# team_throttle_control_draft_2.net
KiCad netlist of a schematic drawn in Altium Designer
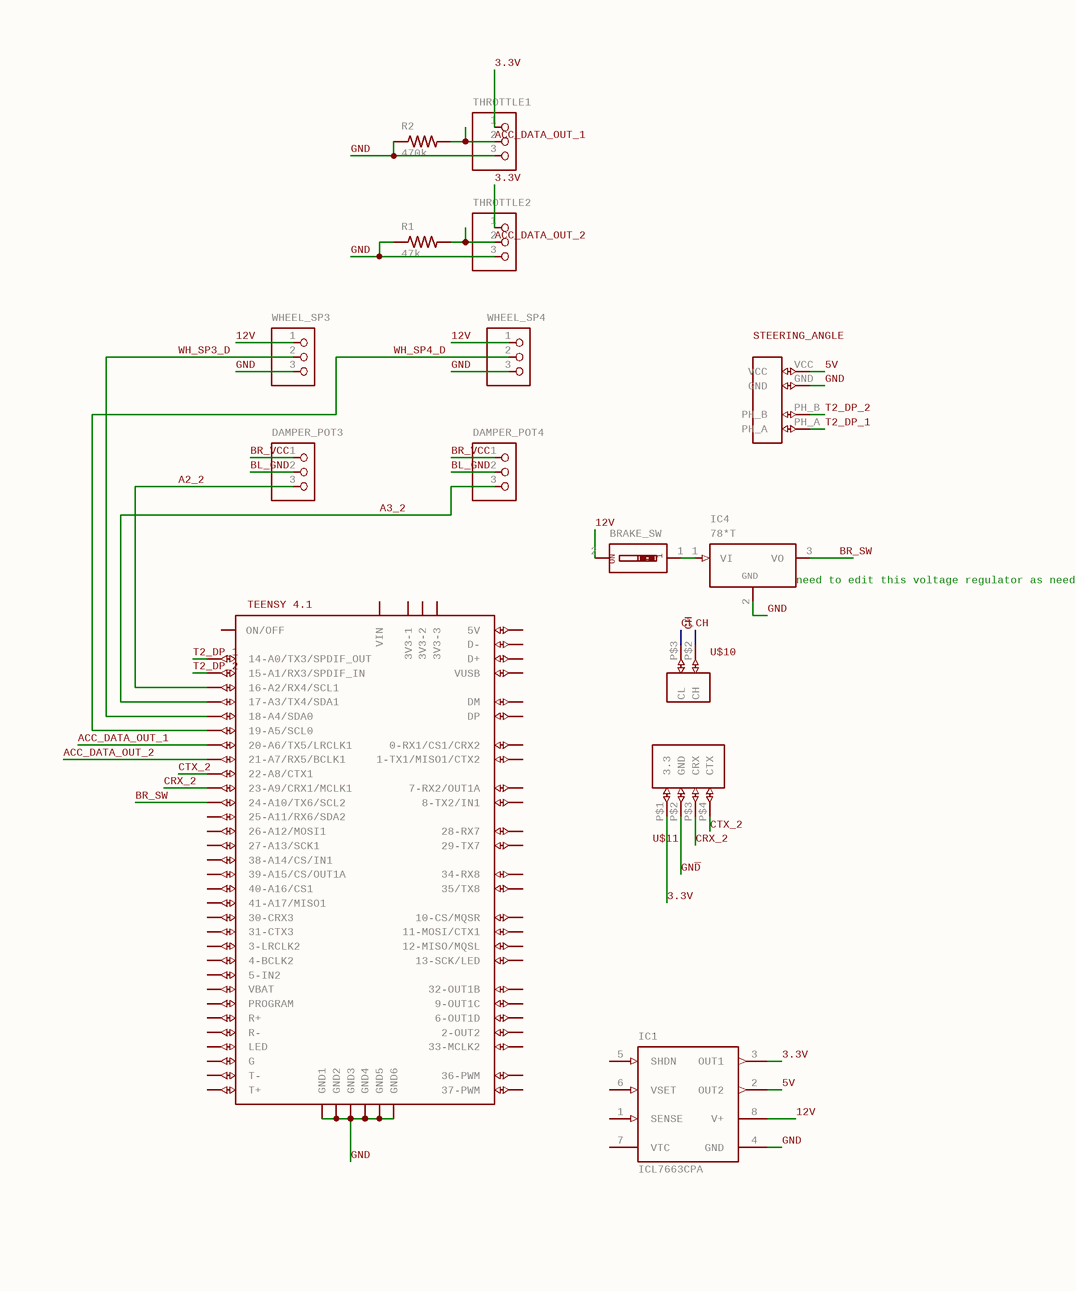
[diagram p0: team throttle control draft 2.SchDoc]

(export (version "E")
  (design (tool "Eeschema 10.0.6"))
  (components
    (comp (ref "BRAKE_SW")
      (value "SW_DIP-1")
      (footprint "EDG-01")
      (description "DIP SWITCH")
      (fields (field (name "1") "1") (field (name "ON") "ON"))
      (libsource (lib "special") (part "SW_DIP-1"))
    )
    (comp (ref "DAMPER_POT3")
      (value "PINHD-1X3CB")
      (footprint "1X03-CLEANBIG")
      (description "PIN HEADER")
      (libsource (lib "adafruit") (part "PINHD-1X3CB"))
    )
    (comp (ref "DAMPER_POT4")
      (value "PINHD-1X3CB")
      (footprint "1X03-CLEANBIG")
      (description "PIN HEADER")
      (libsource (lib "adafruit") (part "PINHD-1X3CB"))
    )
    (comp (ref "IC1")
      (value "ICL7663CPA")
      (footprint "DIL08")
      (description "Positive VOLTAGE REGULATOR")
      (fields (field (name "MF") "MF") (field (name "MPN") "MPN"))
      (libsource (lib "maxim") (part "ICL7663CPA"))
    )
    (comp (ref "IC4")
      (value "78*T")
      (footprint "TO220H")
      (description "Positive VOLTAGE REGULATOR   Added bigger pads to the TO-92 package")
      (fields (field (name "GND") "GND"))
      (libsource (lib "adafruit") (part "78*T"))
    )
    (comp (ref "R1")
      (value "47k")
      (footprint "0204/7")
      (description "RESISTOR, American symbol")
      (libsource (lib "rcl") (part "R-US_0204/7"))
    )
    (comp (ref "R2")
      (value "470k")
      (footprint "0204/7")
      (description "RESISTOR, American symbol")
      (libsource (lib "rcl") (part "R-US_0204/7"))
    )
    (comp (ref "STEERING_ANGLE")
      (value "ROTARY_ENCODER")
      (footprint "ROTARY_ENCODER")
      (libsource (lib "F-E library custom components") (part "ROTARY_ENCODER"))
    )
    (comp (ref "THROTTLE1")
      (value "PINHD-1X3")
      (footprint "1X03")
      (description "PIN HEADER")
      (libsource (lib "adafruit") (part "PINHD-1X3"))
    )
    (comp (ref "THROTTLE2")
      (value "PINHD-1X3")
      (footprint "1X03")
      (description "PIN HEADER")
      (libsource (lib "adafruit") (part "PINHD-1X3"))
    )
    (comp (ref "U$3")
      (value "TEENSY41")
      (footprint "TEENSY41")
      (fields (field (name "TEENSY4.1") "TEENSY 4.1"))
      (libsource (lib "teensy") (part "TEENSY41"))
    )
    (comp (ref "U$10")
      (value "CAN_BUS")
      (footprint "CAN_BUS")
      (libsource (lib "F-E library custom components") (part "CAN_BUS"))
    )
    (comp (ref "U$11")
      (value "CAN_TEE")
      (footprint "CAN_TEN")
      (libsource (lib "F-E library custom components") (part "CAN_TEE"))
    )
    (comp (ref "WHEEL_SP3")
      (value "PINHD-1X3")
      (footprint "1X03")
      (description "PIN HEADER")
      (libsource (lib "adafruit") (part "PINHD-1X3"))
    )
    (comp (ref "WHEEL_SP4")
      (value "PINHD-1X3")
      (footprint "1X03")
      (description "PIN HEADER")
      (libsource (lib "adafruit") (part "PINHD-1X3"))
    )
  )
  (nets
    (net (code "3") (name "/3.3V") (class "Default")
      (node (ref "IC1") (pin "3") (pinfunction "OUT1_3") (pintype "output"))
      (node (ref "THROTTLE1") (pin "1") (pinfunction "1_1") (pintype "passive"))
      (node (ref "THROTTLE2") (pin "1") (pinfunction "1_1") (pintype "passive"))
      (node (ref "U$11") (pin "P$1") (pinfunction "3.3_P$1") (pintype "bidirectional"))
    )
    (net (code "4") (name "/5V") (class "Default")
      (node (ref "IC1") (pin "2") (pinfunction "OUT2_2") (pintype "output"))
      (node (ref "STEERING_ANGLE") (pin "VCC") (pinfunction "VCC_VCC") (pintype "bidirectional"))
    )
    (net (code "5") (name "/12V") (class "Default")
      (node (ref "BRAKE_SW") (pin "2") (pinfunction "2_2") (pintype "passive"))
      (node (ref "IC1") (pin "8") (pinfunction "V+_8") (pintype "power_in"))
      (node (ref "WHEEL_SP3") (pin "1") (pinfunction "1_1") (pintype "passive"))
      (node (ref "WHEEL_SP4") (pin "1") (pinfunction "1_1") (pintype "passive"))
    )
    (net (code "6") (name "/A2_2") (class "Default")
      (node (ref "DAMPER_POT3") (pin "3") (pinfunction "3_3") (pintype "passive"))
      (node (ref "U$3") (pin "16-A2/RX4/SCL1") (pinfunction "16-A2/RX4/SCL1_16-A2/RX4/SCL1") (pintype "bidirectional"))
    )
    (net (code "7") (name "/A3_2") (class "Default")
      (node (ref "DAMPER_POT4") (pin "3") (pinfunction "3_3") (pintype "passive"))
      (node (ref "U$3") (pin "17-A3/TX4/SDA1") (pinfunction "17-A3/TX4/SDA1_17-A3/TX4/SDA1") (pintype "bidirectional"))
    )
    (net (code "8") (name "/ACC_DATA_OUT_1") (class "Default")
      (node (ref "R2") (pin "2") (pinfunction "2_2") (pintype "passive"))
      (node (ref "THROTTLE1") (pin "2") (pinfunction "2_2") (pintype "passive"))
      (node (ref "U$3") (pin "20-A6/TX5/LRCLK1") (pinfunction "20-A6/TX5/LRCLK1_20-A6/TX5/LRCLK1") (pintype "bidirectional"))
    )
    (net (code "9") (name "/ACC_DATA_OUT_2") (class "Default")
      (node (ref "R1") (pin "2") (pinfunction "2_2") (pintype "passive"))
      (node (ref "THROTTLE2") (pin "2") (pinfunction "2_2") (pintype "passive"))
      (node (ref "U$3") (pin "21-A7/RX5/BCLK1") (pinfunction "21-A7/RX5/BCLK1_21-A7/RX5/BCLK1") (pintype "bidirectional"))
    )
    (net (code "10") (name "/BL_GND") (class "Default")
      (node (ref "DAMPER_POT3") (pin "2") (pinfunction "2_2") (pintype "passive"))
      (node (ref "DAMPER_POT4") (pin "2") (pinfunction "2_2") (pintype "passive"))
    )
    (net (code "11") (name "/BR_SW") (class "Default")
      (node (ref "IC4") (pin "3") (pinfunction "VO_3") (pintype "passive"))
      (node (ref "U$3") (pin "24-A10/TX6/SCL2") (pinfunction "24-A10/TX6/SCL2_24-A10/TX6/SCL2") (pintype "bidirectional"))
    )
    (net (code "12") (name "/BR_VCC") (class "Default")
      (node (ref "DAMPER_POT3") (pin "1") (pinfunction "1_1") (pintype "passive"))
      (node (ref "DAMPER_POT4") (pin "1") (pinfunction "1_1") (pintype "passive"))
    )
    (net (code "13") (name "/CRX_2") (class "Default")
      (node (ref "U$11") (pin "P$3") (pinfunction "CRX_P$3") (pintype "bidirectional"))
      (node (ref "U$3") (pin "23-A9/CRX1/MCLK1") (pinfunction "23-A9/CRX1/MCLK1_23-A9/CRX1/MCLK1") (pintype "bidirectional"))
    )
    (net (code "14") (name "/CTX_2") (class "Default")
      (node (ref "U$11") (pin "P$4") (pinfunction "CTX_P$4") (pintype "bidirectional"))
      (node (ref "U$3") (pin "22-A8/CTX1") (pinfunction "22-A8/CTX1_22-A8/CTX1") (pintype "bidirectional"))
    )
    (net (code "15") (name "/GND") (class "Default")
      (node (ref "IC1") (pin "4") (pinfunction "GND_4") (pintype "power_in"))
      (node (ref "IC4") (pin "2") (pinfunction "GND_2") (pintype "passive"))
      (node (ref "R1") (pin "1") (pinfunction "1_1") (pintype "passive"))
      (node (ref "R2") (pin "1") (pinfunction "1_1") (pintype "passive"))
      (node (ref "STEERING_ANGLE") (pin "GND") (pinfunction "GND_GND") (pintype "bidirectional"))
      (node (ref "THROTTLE1") (pin "3") (pinfunction "3_3") (pintype "passive"))
      (node (ref "THROTTLE2") (pin "3") (pinfunction "3_3") (pintype "passive"))
      (node (ref "U$3") (pin "GND1") (pinfunction "GND1_GND1") (pintype "bidirectional"))
      (node (ref "U$3") (pin "GND2") (pinfunction "GND2_GND2") (pintype "bidirectional"))
      (node (ref "U$3") (pin "GND3") (pinfunction "GND3_GND3") (pintype "bidirectional"))
      (node (ref "U$3") (pin "GND4") (pinfunction "GND4_GND4") (pintype "bidirectional"))
      (node (ref "U$3") (pin "GND5") (pinfunction "GND5_GND5") (pintype "bidirectional"))
      (node (ref "U$3") (pin "GND6") (pinfunction "GND6_GND6") (pintype "bidirectional"))
      (node (ref "WHEEL_SP3") (pin "3") (pinfunction "3_3") (pintype "passive"))
      (node (ref "WHEEL_SP4") (pin "3") (pinfunction "3_3") (pintype "passive"))
    )
    (net (code "16") (name "/GN~{D}") (class "Default")
      (node (ref "U$11") (pin "P$2") (pinfunction "GND_P$2") (pintype "bidirectional"))
    )
    (net (code "17") (name "/T2_DP_1") (class "Default")
      (node (ref "STEERING_ANGLE") (pin "PH_A") (pinfunction "PH_A_PH_A") (pintype "bidirectional"))
      (node (ref "U$3") (pin "14-A0/TX3/SPDIF_OUT") (pinfunction "14-A0/TX3/SPDIF_OUT_14-A0/TX3/SPDIF_OUT") (pintype "bidirectional"))
    )
    (net (code "18") (name "/T2_DP_2") (class "Default")
      (node (ref "STEERING_ANGLE") (pin "PH_B") (pinfunction "PH_B_PH_B") (pintype "bidirectional"))
      (node (ref "U$3") (pin "15-A1/RX3/SPDIF_IN") (pinfunction "15-A1/RX3/SPDIF_IN_15-A1/RX3/SPDIF_IN") (pintype "bidirectional"))
    )
    (net (code "19") (name "/WH_SP3_D") (class "Default")
      (node (ref "U$3") (pin "18-A4/SDA0") (pinfunction "18-A4/SDA0_18-A4/SDA0") (pintype "bidirectional"))
      (node (ref "WHEEL_SP3") (pin "2") (pinfunction "2_2") (pintype "passive"))
    )
    (net (code "20") (name "/WH_SP4_D") (class "Default")
      (node (ref "U$3") (pin "19-A5/SCL0") (pinfunction "19-A5/SCL0_19-A5/SCL0") (pintype "bidirectional"))
      (node (ref "WHEEL_SP4") (pin "2") (pinfunction "2_2") (pintype "passive"))
    )
    (net (code "21") (name "/{CH}") (class "Default")
      (node (ref "U$10") (pin "P$2") (pinfunction "CH_P$2") (pintype "bidirectional"))
    )
    (net (code "22") (name "/{CL}") (class "Default")
      (node (ref "U$10") (pin "P$3") (pinfunction "CL_P$3") (pintype "bidirectional"))
    )
    (net (code "23") (name "Net-(IC4-VI)") (class "Default")
      (node (ref "BRAKE_SW") (pin "1") (pinfunction "1_1") (pintype "passive"))
      (node (ref "IC4") (pin "1") (pinfunction "VI_1") (pintype "input"))
    )
    (net (code "24") (name "unconnected-(IC1-SENSE-Pad1)") (class "Default")
      (node (ref "IC1") (pin "1") (pinfunction "SENSE_1") (pintype "input"))
    )
    (net (code "25") (name "unconnected-(IC1-SHDN-Pad5)") (class "Default")
      (node (ref "IC1") (pin "5") (pinfunction "SHDN_5") (pintype "input"))
    )
    (net (code "26") (name "unconnected-(IC1-VSET-Pad6)") (class "Default")
      (node (ref "IC1") (pin "6") (pinfunction "VSET_6") (pintype "input"))
    )
    (net (code "27") (name "unconnected-(IC1-VTC-Pad7)") (class "Default")
      (node (ref "IC1") (pin "7") (pinfunction "VTC_7") (pintype "passive"))
    )
    (net (code "28") (name "unconnected-(U$3-5V-Pad+5V)") (class "Default")
      (node (ref "U$3") (pin "+5V") (pinfunction "5V_+5V") (pintype "bidirectional"))
    )
    (net (code "29") (name "unconnected-(U$3-8-TX2{slash}IN1-Pad8-TX2{slash}IN2)") (class "Default")
      (node (ref "U$3") (pin "8-TX2/IN2") (pinfunction "8-TX2/IN1_8-TX2/IN2") (pintype "bidirectional"))
    )
    (net (code "30") (name "unconnected-(U$3-10-CS{slash}MQSR-Pad10-C~{S}MQSR)") (class "Default")
      (node (ref "U$3") (pin "10-C~{S}MQSR") (pinfunction "10-CS/MQSR_10-C~{S}MQSR") (pintype "bidirectional"))
    )
    (net (code "31") (name "unconnected-(U$3-35{slash}TX8-Pad35-TX8)") (class "Default")
      (node (ref "U$3") (pin "35-TX8") (pinfunction "35/TX8_35-TX8") (pintype "bidirectional"))
    )
    (net (code "32") (name "unconnected-(U$3-Pad0-RX1{slash}CS1{slash}CRX2)") (class "Default")
      (node (ref "U$3") (pin "0-RX1/CS1/CRX2") (pinfunction "0-RX1/CS1/CRX2_0-RX1/CS1/CRX2") (pintype "bidirectional"))
    )
    (net (code "33") (name "unconnected-(U$3-Pad1-TX1{slash}MISO1{slash}CTX2)") (class "Default")
      (node (ref "U$3") (pin "1-TX1/MISO1/CTX2") (pinfunction "1-TX1/MISO1/CTX2_1-TX1/MISO1/CTX2") (pintype "bidirectional"))
    )
    (net (code "34") (name "unconnected-(U$3-Pad2-OUT2)") (class "Default")
      (node (ref "U$3") (pin "2-OUT2") (pinfunction "2-OUT2_2-OUT2") (pintype "bidirectional"))
    )
    (net (code "35") (name "unconnected-(U$3-Pad3-LRCLK2)") (class "Default")
      (node (ref "U$3") (pin "3-LRCLK2") (pinfunction "3-LRCLK2_3-LRCLK2") (pintype "bidirectional"))
    )
    (net (code "36") (name "unconnected-(U$3-Pad3V3-1)") (class "Default")
      (node (ref "U$3") (pin "3V3-1") (pinfunction "3V3-1_3V3-1") (pintype "bidirectional"))
    )
    (net (code "37") (name "unconnected-(U$3-Pad3V3-2)") (class "Default")
      (node (ref "U$3") (pin "3V3-2") (pinfunction "3V3-2_3V3-2") (pintype "bidirectional"))
    )
    (net (code "38") (name "unconnected-(U$3-Pad3V3-3)") (class "Default")
      (node (ref "U$3") (pin "3V3-3") (pinfunction "3V3-3_3V3-3") (pintype "bidirectional"))
    )
    (net (code "39") (name "unconnected-(U$3-Pad4-BCLK2)") (class "Default")
      (node (ref "U$3") (pin "4-BCLK2") (pinfunction "4-BCLK2_4-BCLK2") (pintype "bidirectional"))
    )
    (net (code "40") (name "unconnected-(U$3-Pad5-IN2)") (class "Default")
      (node (ref "U$3") (pin "5-IN2") (pinfunction "5-IN2_5-IN2") (pintype "bidirectional"))
    )
    (net (code "41") (name "unconnected-(U$3-Pad6-OUT1D)") (class "Default")
      (node (ref "U$3") (pin "6-OUT1D") (pinfunction "6-OUT1D_6-OUT1D") (pintype "bidirectional"))
    )
    (net (code "42") (name "unconnected-(U$3-Pad7-RX2{slash}OUT1A)") (class "Default")
      (node (ref "U$3") (pin "7-RX2/OUT1A") (pinfunction "7-RX2/OUT1A_7-RX2/OUT1A") (pintype "bidirectional"))
    )
    (net (code "43") (name "unconnected-(U$3-Pad9-OUT1C)") (class "Default")
      (node (ref "U$3") (pin "9-OUT1C") (pinfunction "9-OUT1C_9-OUT1C") (pintype "bidirectional"))
    )
    (net (code "44") (name "unconnected-(U$3-Pad11-MOSI{slash}CTX1)") (class "Default")
      (node (ref "U$3") (pin "11-MOSI/CTX1") (pinfunction "11-MOSI/CTX1_11-MOSI/CTX1") (pintype "bidirectional"))
    )
    (net (code "45") (name "unconnected-(U$3-Pad12-MISO{slash}MQSL)") (class "Default")
      (node (ref "U$3") (pin "12-MISO/MQSL") (pinfunction "12-MISO/MQSL_12-MISO/MQSL") (pintype "bidirectional"))
    )
    (net (code "46") (name "unconnected-(U$3-Pad13-SCK{slash}LED)") (class "Default")
      (node (ref "U$3") (pin "13-SCK/LED") (pinfunction "13-SCK/LED_13-SCK/LED") (pintype "bidirectional"))
    )
    (net (code "47") (name "unconnected-(U$3-Pad25-A11{slash}RX6{slash}SDA2)") (class "Default")
      (node (ref "U$3") (pin "25-A11/RX6/SDA2") (pinfunction "25-A11/RX6/SDA2_25-A11/RX6/SDA2") (pintype "bidirectional"))
    )
    (net (code "48") (name "unconnected-(U$3-Pad26-A12{slash}MOSI1)") (class "Default")
      (node (ref "U$3") (pin "26-A12/MOSI1") (pinfunction "26-A12/MOSI1_26-A12/MOSI1") (pintype "bidirectional"))
    )
    (net (code "49") (name "unconnected-(U$3-Pad27-A13{slash}SCK1)") (class "Default")
      (node (ref "U$3") (pin "27-A13/SCK1") (pinfunction "27-A13/SCK1_27-A13/SCK1") (pintype "bidirectional"))
    )
    (net (code "50") (name "unconnected-(U$3-Pad28-RX7)") (class "Default")
      (node (ref "U$3") (pin "28-RX7") (pinfunction "28-RX7_28-RX7") (pintype "bidirectional"))
    )
    (net (code "51") (name "unconnected-(U$3-Pad29-TX7)") (class "Default")
      (node (ref "U$3") (pin "29-TX7") (pinfunction "29-TX7_29-TX7") (pintype "bidirectional"))
    )
    (net (code "52") (name "unconnected-(U$3-Pad30-CRX3)") (class "Default")
      (node (ref "U$3") (pin "30-CRX3") (pinfunction "30-CRX3_30-CRX3") (pintype "bidirectional"))
    )
    (net (code "53") (name "unconnected-(U$3-Pad31-CTX3)") (class "Default")
      (node (ref "U$3") (pin "31-CTX3") (pinfunction "31-CTX3_31-CTX3") (pintype "bidirectional"))
    )
    (net (code "54") (name "unconnected-(U$3-Pad32-OUT1B)") (class "Default")
      (node (ref "U$3") (pin "32-OUT1B") (pinfunction "32-OUT1B_32-OUT1B") (pintype "bidirectional"))
    )
    (net (code "55") (name "unconnected-(U$3-Pad33-MCLK2)") (class "Default")
      (node (ref "U$3") (pin "33-MCLK2") (pinfunction "33-MCLK2_33-MCLK2") (pintype "bidirectional"))
    )
    (net (code "56") (name "unconnected-(U$3-Pad34-RX8)") (class "Default")
      (node (ref "U$3") (pin "34-RX8") (pinfunction "34-RX8_34-RX8") (pintype "bidirectional"))
    )
    (net (code "57") (name "unconnected-(U$3-Pad36-PWM)") (class "Default")
      (node (ref "U$3") (pin "36-PWM") (pinfunction "36-PWM_36-PWM") (pintype "bidirectional"))
    )
    (net (code "58") (name "unconnected-(U$3-Pad37-PWM)") (class "Default")
      (node (ref "U$3") (pin "37-PWM") (pinfunction "37-PWM_37-PWM") (pintype "bidirectional"))
    )
    (net (code "59") (name "unconnected-(U$3-Pad38-A14{slash}CS{slash}IN1)") (class "Default")
      (node (ref "U$3") (pin "38-A14/CS/IN1") (pinfunction "38-A14/CS/IN1_38-A14/CS/IN1") (pintype "bidirectional"))
    )
    (net (code "60") (name "unconnected-(U$3-Pad39-A15{slash}CS{slash}OUT1A)") (class "Default")
      (node (ref "U$3") (pin "39-A15/CS/OUT1A") (pinfunction "39-A15/CS/OUT1A_39-A15/CS/OUT1A") (pintype "bidirectional"))
    )
    (net (code "61") (name "unconnected-(U$3-Pad40-A16{slash}CS1)") (class "Default")
      (node (ref "U$3") (pin "40-A16/CS1") (pinfunction "40-A16/CS1_40-A16/CS1") (pintype "bidirectional"))
    )
    (net (code "62") (name "unconnected-(U$3-Pad41-A17{slash}MISO1)") (class "Default")
      (node (ref "U$3") (pin "41-A17/MISO1") (pinfunction "41-A17/MISO1_41-A17/MISO1") (pintype "bidirectional"))
    )
    (net (code "63") (name "unconnected-(U$3-PadD+)") (class "Default")
      (node (ref "U$3") (pin "D+") (pinfunction "D+_D+") (pintype "bidirectional"))
    )
    (net (code "64") (name "unconnected-(U$3-PadD-)") (class "Default")
      (node (ref "U$3") (pin "D-") (pinfunction "D-_D-") (pintype "bidirectional"))
    )
    (net (code "65") (name "unconnected-(U$3-PadDM)") (class "Default")
      (node (ref "U$3") (pin "DM") (pinfunction "DM_DM") (pintype "bidirectional"))
    )
    (net (code "66") (name "unconnected-(U$3-PadDP)") (class "Default")
      (node (ref "U$3") (pin "DP") (pinfunction "DP_DP") (pintype "bidirectional"))
    )
    (net (code "67") (name "unconnected-(U$3-PadG)") (class "Default")
      (node (ref "U$3") (pin "G") (pinfunction "G_G") (pintype "bidirectional"))
    )
    (net (code "68") (name "unconnected-(U$3-PadLED)") (class "Default")
      (node (ref "U$3") (pin "LED") (pinfunction "LED_LED") (pintype "bidirectional"))
    )
    (net (code "69") (name "unconnected-(U$3-PadON{slash}OFF)") (class "Default")
      (node (ref "U$3") (pin "ON/OFF") (pinfunction "ON/OFF_ON/OFF") (pintype "bidirectional"))
    )
    (net (code "70") (name "unconnected-(U$3-PadPROGRAM)") (class "Default")
      (node (ref "U$3") (pin "PROGRAM") (pinfunction "PROGRAM_PROGRAM") (pintype "bidirectional"))
    )
    (net (code "71") (name "unconnected-(U$3-PadR+)") (class "Default")
      (node (ref "U$3") (pin "R+") (pinfunction "R+_R+") (pintype "bidirectional"))
    )
    (net (code "72") (name "unconnected-(U$3-PadR-)") (class "Default")
      (node (ref "U$3") (pin "R-") (pinfunction "R-_R-") (pintype "bidirectional"))
    )
    (net (code "73") (name "unconnected-(U$3-PadT+)") (class "Default")
      (node (ref "U$3") (pin "T+") (pinfunction "T+_T+") (pintype "bidirectional"))
    )
    (net (code "74") (name "unconnected-(U$3-PadT-)") (class "Default")
      (node (ref "U$3") (pin "T-") (pinfunction "T-_T-") (pintype "bidirectional"))
    )
    (net (code "75") (name "unconnected-(U$3-PadVBAT)") (class "Default")
      (node (ref "U$3") (pin "VBAT") (pinfunction "VBAT_VBAT") (pintype "bidirectional"))
    )
    (net (code "76") (name "unconnected-(U$3-PadVIN)") (class "Default")
      (node (ref "U$3") (pin "VIN") (pinfunction "VIN_VIN") (pintype "bidirectional"))
    )
    (net (code "77") (name "unconnected-(U$3-PadVUSB)") (class "Default")
      (node (ref "U$3") (pin "VUSB") (pinfunction "VUSB_VUSB") (pintype "bidirectional"))
    )
  )
)
